# WATERALARM_V1_2.net
KiCad netlist of a schematic drawn in Altium Designer
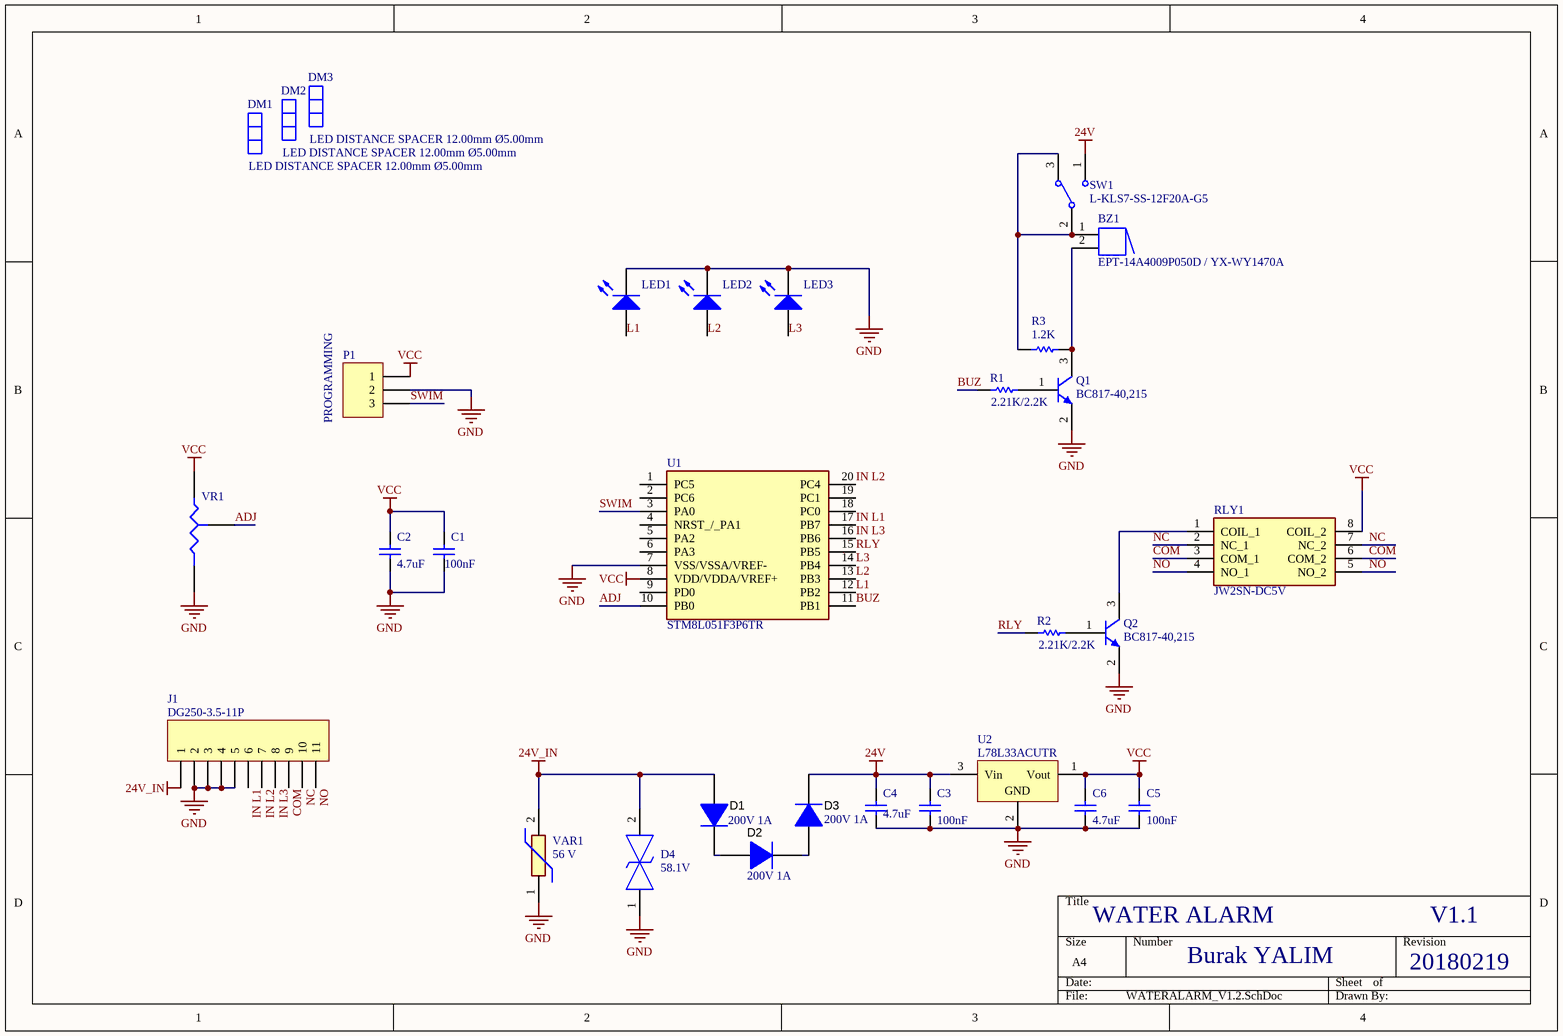
[diagram p0: WATERALARM_V1.2.SchDoc]

(export (version "E")
  (design (tool "Eeschema 10.0.6"))
  (components
    (comp (ref "BZ1")
      (value "EPT-14A4009P050D / YX-WY1470A")
      (footprint "piezo buzzer")
      (description "BUZZER PIEZO W/O CIRCUIT 9V 4-KHZ THT")
      (fields (field (name "MANUFACTURER") "SANCO / YXDZ"))
      (libsource (lib "Miscellaneous Devices") (part "Buzzer"))
    )
    (comp (ref "C1")
      (value "100nF")
      (footprint "C0805-N")
      (description "MLCC (2012) 0805 100nF 50VDC ±10% X7R")
      (fields
        (field (name "MANUFACTURER") "SAMSUNG")
        (field (name "MANUFACTURER PART NUMBER") "CL21B104KBCNNNL")
      )
      (libsource (lib "Miscellaneous Devices") (part "Cap"))
    )
    (comp (ref "C2")
      (value "4.7uF")
      (footprint "C0805-N")
      (description "MLCC (2012) 0805 4.7uF 50VDC ±10% X5R")
      (fields
        (field (name "MANUFACTURER") "SAMSUNG")
        (field (name "MANUFACTURER PART NUMBER") "CL21A475KBQNNNE")
      )
      (libsource (lib "Miscellaneous Devices") (part "Cap"))
    )
    (comp (ref "C3")
      (value "100nF")
      (footprint "C0805-N")
      (description "MLCC (2012) 0805 100nF 50VDC ±10% X7R")
      (fields
        (field (name "MANUFACTURER") "SAMSUNG")
        (field (name "MANUFACTURER PART NUMBER") "CL21B104KBCNNNL")
      )
      (libsource (lib "Miscellaneous Devices") (part "Cap"))
    )
    (comp (ref "C4")
      (value "4.7uF")
      (footprint "C0805-N")
      (description "MLCC (2012) 0805 4.7uF 50VDC ±10% X5R")
      (fields
        (field (name "MANUFACTURER") "SAMSUNG")
        (field (name "MANUFACTURER PART NUMBER") "CL21A475KBQNNNE")
      )
      (libsource (lib "Miscellaneous Devices") (part "Cap"))
    )
    (comp (ref "C5")
      (value "100nF")
      (footprint "C0805-N")
      (description "MLCC (2012) 0805 100nF 50VDC ±10% X7R")
      (fields
        (field (name "MANUFACTURER") "SAMSUNG")
        (field (name "MANUFACTURER PART NUMBER") "CL21B104KBCNNNL")
      )
      (libsource (lib "Miscellaneous Devices") (part "Cap"))
    )
    (comp (ref "C6")
      (value "4.7uF")
      (footprint "C0805-N")
      (description "MLCC (2012) 0805 4.7uF 50VDC ±10% X5R")
      (fields
        (field (name "MANUFACTURER") "SAMSUNG")
        (field (name "MANUFACTURER PART NUMBER") "CL21A475KBQNNNE")
      )
      (libsource (lib "Miscellaneous Devices") (part "Cap"))
    )
    (comp (ref "D1")
      (value "200V 1A")
      (footprint "SMA")
      (description "DIODE U.FAST SINGLE 1A 200V DO214AC (SMA) SMT")
      (fields
        (field (name "MANUFACTURER PART NUMBER") "US1D_R1_00001 / US1D-SMA-MDD")
        (field (name "MANUFACTURER") "ON Semiconductor /  MDD(Microdiode Semiconductor)")
      )
      (libsource (lib "PMP30720_RevA") (part "MURA160T3G"))
    )
    (comp (ref "D2")
      (value "200V 1A")
      (footprint "SMA")
      (description "DIODE U.FAST SINGLE 1A 200V DO214AC (SMA) SMT")
      (fields
        (field (name "MANUFACTURER PART NUMBER") "US1D_R1_00001 / US1D-SMA-MDD")
        (field (name "MANUFACTURER") "ON Semiconductor /  MDD(Microdiode Semiconductor)")
      )
      (libsource (lib "PMP30720_RevA") (part "MURA160T3G"))
    )
    (comp (ref "D3")
      (value "200V 1A")
      (footprint "SMA")
      (description "DIODE U.FAST SINGLE 1A 200V DO214AC (SMA) SMT")
      (fields
        (field (name "MANUFACTURER PART NUMBER") "US1D_R1_00001 / US1D-SMA-MDD")
        (field (name "MANUFACTURER") "ON Semiconductor /  MDD(Microdiode Semiconductor)")
      )
      (libsource (lib "PMP30720_RevA") (part "MURA160T3G"))
    )
    (comp (ref "D4")
      (value "58.1V")
      (footprint "SamacSys:DIONM5127X250N")
      (description "58.1V Clamp 6.9A Ipp Tvs Diode Surface Mount DO-214AC (SMA)")
      (fields
        (field (name "MANUFACTURER") "YAGEO / MDD(Microdiode Semiconductor)")
        (field (name "MANUFACTURER PART NUMBER") "SMAJ36CA/TR7 / SMAJ36CA-UMW")
      )
      (libsource (lib "*") (part "SMAJ36CA-AT_TR7"))
    )
    (comp (ref "DM1")
      (value "LED DISTANCE SPACER 12.00mm Ø5.00mm")
      (description "LED DISTANCE SPACER 12.00mm NONE Ø5.00mm")
      (fields
        (field (name "MANUFACTURER") "KLS ELECTRONIC")
        (field (name "MANUFACTURER PART NUMBER") "L-KLS8-0108-LED-12")
      )
      (libsource (lib "GentekConnectorLib") (part "DISTANCE 11MM M3"))
    )
    (comp (ref "DM2")
      (value "LED DISTANCE SPACER 12.00mm Ø5.00mm")
      (description "LED DISTANCE SPACER 12.00mm NONE Ø5.00mm")
      (fields
        (field (name "MANUFACTURER") "KLS ELECTRONIC")
        (field (name "MANUFACTURER PART NUMBER") "L-KLS8-0108-LED-12")
      )
      (libsource (lib "GentekConnectorLib") (part "DISTANCE 11MM M3"))
    )
    (comp (ref "DM3")
      (value "LED DISTANCE SPACER 12.00mm Ø5.00mm")
      (description "LED DISTANCE SPACER 12.00mm NONE Ø5.00mm")
      (fields
        (field (name "MANUFACTURER") "KLS ELECTRONIC")
        (field (name "MANUFACTURER PART NUMBER") "L-KLS8-0108-LED-12")
      )
      (libsource (lib "GentekConnectorLib") (part "DISTANCE 11MM M3"))
    )
    (comp (ref "J1")
      (value "DG250-3.5-11P")
      (footprint "11 pin Terminal sping loaded")
      (description "TERM.BLK.3.50MM 11P PCB TYPE GRAY GAOSONG")
      (fields (field (name "MANUFACTURER") "DEGSON/GAOSONG"))
      (libsource (lib "WATERALARM_V1.1") (part "DG250-3.5-11P"))
    )
    (comp (ref "LED1")
      (value "3R4HD-7-TB")
      (footprint "led 3mm")
      (description "LED 3MM RED 30mcd 35° RED/DIFFUSED")
      (fields (field (name "MANUFACTURER") "STRONG BASE"))
      (libsource (lib "Miscellaneous Devices") (part "LED2"))
    )
    (comp (ref "LED2")
      (value "3R4HD-7-TB")
      (footprint "led 3mm")
      (description "LED 3MM RED 30mcd 35° RED/DIFFUSED")
      (fields (field (name "MANUFACTURER") "STRONG BASE"))
      (libsource (lib "Miscellaneous Devices") (part "LED2"))
    )
    (comp (ref "LED3")
      (value "3R4HD-7-TB")
      (footprint "led 3mm")
      (description "LED 3MM RED 30mcd 35° RED/DIFFUSED")
      (fields (field (name "MANUFACTURER") "STRONG BASE"))
      (libsource (lib "Miscellaneous Devices") (part "LED2"))
    )
    (comp (ref "P1")
      (value "PROGRAMMING")
      (footprint "HDR1X3")
      (description "Header, 3-Pin")
      (libsource (lib "Miscellaneous Connectors") (part "Header 3"))
    )
    (comp (ref "Q1")
      (value "BC817-40,215")
      (footprint "SOT-23")
      (description "TRANSISTOR DIS.500mA 45V NPN SOT23 GEN. SMT")
      (fields (field (name "MANUFACTURER") "NXP"))
      (libsource (lib "Miscellaneous Devices") (part "NPN"))
    )
    (comp (ref "Q2")
      (value "BC817-40,215")
      (footprint "SOT-23")
      (description "TRANSISTOR DIS.500mA 45V NPN SOT23 GEN. SMT")
      (fields (field (name "MANUFACTURER") "NXP"))
      (libsource (lib "Miscellaneous Devices") (part "NPN"))
    )
    (comp (ref "R1")
      (value "2.21K/2.2K")
      (footprint "C0805-N")
      (description "RES.(2012) 0805 2.21K/2.2K Ohms 1%/5% 1/8W-S 100PPM")
      (fields
        (field (name "MANUFACTURER") "ROYALOHM")
        (field (name "MANUFACTURER PART NUMBER") "0805S8F2211T5E/0805S8J0222T5E")
      )
      (libsource (lib "Miscellaneous Devices") (part "Res1"))
    )
    (comp (ref "R2")
      (value "2.21K/2.2K")
      (footprint "C0805-N")
      (description "RES.(2012) 0805 2.21K/2.2K Ohms 1%/5% 1/8W-S 100PPM")
      (fields
        (field (name "MANUFACTURER") "ROYALOHM")
        (field (name "MANUFACTURER PART NUMBER") "0805S8F2211T5E/0805S8J0222T5E")
      )
      (libsource (lib "Miscellaneous Devices") (part "Res1"))
    )
    (comp (ref "R3")
      (value "1.2K")
      (footprint "C1210")
      (description "RES.(3225) 1210 1.2K Ohms 5% 1/2W 200PPM")
      (fields
        (field (name "MANUFACTURER") "HOTTECH")
        (field (name "MANUFACTURER PART NUMBER") "RI1210L122JT")
      )
      (libsource (lib "Miscellaneous Devices") (part "Res1"))
    )
    (comp (ref "RLY1")
      (value "JW2SN-DC5V")
      (footprint "SamacSys:JW2SNDC5V")
      (description "General Purpose Relay DPDT (2 Form C) 5VDC Coil Through Hole")
      (fields (field (name "MANUFACTURER") "Panasonic"))
      (libsource (lib "*") (part "JW2SN-DC5V"))
    )
    (comp (ref "SW1")
      (value "L-KLS7-SS-12F20A-G5")
      (footprint "Slide Switch")
      (description "SWITCH SLIDE 1P2T 500mA 50V On-On THT V/T")
      (fields (field (name "MANUFACTURER") "KLS ELECTRONIC"))
      (libsource (lib "Miscellaneous Devices") (part "SW-SPDT"))
    )
    (comp (ref "U1")
      (value "STM8L051F3P6TR")
      (footprint "SamacSys:SOP65P640X120-20N")
      (description "IC-8L051 MCU 8BIT 8K FLASH TSSOP20")
      (fields
        (field (name "MANUFACTURER") "STMicroelectronics")
        (field (name "MOUSER PART NUMBER") "511-STM8L051F3P6TR")
      )
      (libsource (lib "*") (part "STM8L051F3P6TR"))
    )
    (comp (ref "U2")
      (value "L78L33ACUTR")
      (footprint "SOT89M")
      (description "IC-78L33 VOLTAGE REGULATOR 3.3V 100mA SOT89 ST")
      (fields (field (name "MANUFACTURER") "STM"))
      (libsource (lib "Miscellaneous Devices") (part "Volt Reg"))
    )
    (comp (ref "VAR1")
      (value "TVR07470KSY")
      (footprint "SamacSys:ERZV05D180")
      (description "VARISTOR DISC 7MM 47V 250A 30VAC 38VDC THT")
      (fields (field (name "VARISTOR VOLTAGE") "56 V") (field (name "MANUFACTURER") "THINKING"))
      (libsource (lib "*") (part "ERZ-V05D180"))
    )
    (comp (ref "VR1")
      (value "L-KLS4-WH06-2A-103")
      (footprint "Potentiometer")
      (description "TRIMPOT CARBON V 6MM 10K")
      (fields (field (name "MANUFACTURER") "KLS ELECTRONIC"))
      (libsource (lib "Miscellaneous Devices") (part "Res Tap"))
    )
  )
  (nets
    (net (code "1") (name "/ADJ") (class "Default")
      (node (ref "U1") (pin "10") (pinfunction "PB0_10") (pintype "passive"))
      (node (ref "VR1") (pin "3") (pinfunction "TAP_3") (pintype "passive"))
    )
    (net (code "2") (name "/BUZ") (class "Default")
      (node (ref "R1") (pin "2") (pinfunction "2_2") (pintype "passive"))
      (node (ref "U1") (pin "11") (pinfunction "PB1_11") (pintype "passive"))
    )
    (net (code "3") (name "/COM") (class "Default")
      (node (ref "J1") (pin "9") (pinfunction "9_9") (pintype "passive"))
      (node (ref "RLY1") (pin "3") (pinfunction "COM_1_3") (pintype "passive"))
      (node (ref "RLY1") (pin "6") (pinfunction "COM_2_6") (pintype "passive"))
    )
    (net (code "4") (name "/IN L1") (class "Default")
      (node (ref "J1") (pin "6") (pinfunction "6_6") (pintype "passive"))
      (node (ref "U1") (pin "17") (pinfunction "PB7_17") (pintype "passive"))
    )
    (net (code "5") (name "/IN L2") (class "Default")
      (node (ref "J1") (pin "7") (pinfunction "7_7") (pintype "passive"))
      (node (ref "U1") (pin "20") (pinfunction "PC4_20") (pintype "passive"))
    )
    (net (code "6") (name "/IN L3") (class "Default")
      (node (ref "J1") (pin "8") (pinfunction "8_8") (pintype "passive"))
      (node (ref "U1") (pin "16") (pinfunction "PB6_16") (pintype "passive"))
    )
    (net (code "7") (name "/L1") (class "Default")
      (node (ref "LED1") (pin "1") (pinfunction "A_1") (pintype "passive"))
      (node (ref "U1") (pin "12") (pinfunction "PB2_12") (pintype "passive"))
    )
    (net (code "8") (name "/L2") (class "Default")
      (node (ref "LED2") (pin "1") (pinfunction "A_1") (pintype "passive"))
      (node (ref "U1") (pin "13") (pinfunction "PB3_13") (pintype "passive"))
    )
    (net (code "9") (name "/L3") (class "Default")
      (node (ref "LED3") (pin "1") (pinfunction "A_1") (pintype "passive"))
      (node (ref "U1") (pin "14") (pinfunction "PB4_14") (pintype "passive"))
    )
    (net (code "10") (name "/NC") (class "Default")
      (node (ref "J1") (pin "10") (pinfunction "10_10") (pintype "passive"))
      (node (ref "RLY1") (pin "2") (pinfunction "NC_1_2") (pintype "passive"))
      (node (ref "RLY1") (pin "7") (pinfunction "NC_2_7") (pintype "passive"))
    )
    (net (code "11") (name "/NO") (class "Default")
      (node (ref "J1") (pin "11") (pinfunction "11_11") (pintype "passive"))
      (node (ref "RLY1") (pin "4") (pinfunction "NO_1_4") (pintype "passive"))
      (node (ref "RLY1") (pin "5") (pinfunction "NO_2_5") (pintype "passive"))
    )
    (net (code "12") (name "/RLY") (class "Default")
      (node (ref "R2") (pin "2") (pinfunction "2_2") (pintype "passive"))
      (node (ref "U1") (pin "15") (pinfunction "PB5_15") (pintype "passive"))
    )
    (net (code "13") (name "/SWIM") (class "Default")
      (node (ref "P1") (pin "3") (pinfunction "3_3") (pintype "passive"))
      (node (ref "U1") (pin "3") (pinfunction "PA0_3") (pintype "passive"))
    )
    (net (code "14") (name "24V") (class "Default")
      (node (ref "C3") (pin "2") (pinfunction "2_2") (pintype "passive"))
      (node (ref "C4") (pin "2") (pinfunction "2_2") (pintype "passive"))
      (node (ref "D3") (pin "1") (pinfunction "K_1") (pintype "passive"))
      (node (ref "SW1") (pin "1") (pinfunction "1_1") (pintype "passive"))
      (node (ref "U2") (pin "3") (pinfunction "Vin_3") (pintype "passive"))
    )
    (net (code "15") (name "24V_IN") (class "Default")
      (node (ref "D1") (pin "2") (pinfunction "A_2") (pintype "passive"))
      (node (ref "D4") (pin "2") (pinfunction "2_2") (pintype "passive"))
      (node (ref "J1") (pin "1") (pinfunction "1_1") (pintype "passive"))
      (node (ref "VAR1") (pin "2") (pinfunction "2_2") (pintype "passive"))
    )
    (net (code "16") (name "GND") (class "Default")
      (node (ref "C1") (pin "1") (pinfunction "1_1") (pintype "passive"))
      (node (ref "C2") (pin "1") (pinfunction "1_1") (pintype "passive"))
      (node (ref "C3") (pin "1") (pinfunction "1_1") (pintype "passive"))
      (node (ref "C4") (pin "1") (pinfunction "1_1") (pintype "passive"))
      (node (ref "C5") (pin "1") (pinfunction "1_1") (pintype "passive"))
      (node (ref "C6") (pin "1") (pinfunction "1_1") (pintype "passive"))
      (node (ref "D4") (pin "1") (pinfunction "1_1") (pintype "passive"))
      (node (ref "J1") (pin "2") (pinfunction "2_2") (pintype "passive"))
      (node (ref "J1") (pin "3") (pinfunction "3_3") (pintype "passive"))
      (node (ref "J1") (pin "4") (pinfunction "4_4") (pintype "passive"))
      (node (ref "J1") (pin "5") (pinfunction "5_5") (pintype "passive"))
      (node (ref "LED1") (pin "2") (pinfunction "K_2") (pintype "passive"))
      (node (ref "LED2") (pin "2") (pinfunction "K_2") (pintype "passive"))
      (node (ref "LED3") (pin "2") (pinfunction "K_2") (pintype "passive"))
      (node (ref "P1") (pin "2") (pinfunction "2_2") (pintype "passive"))
      (node (ref "Q1") (pin "2") (pinfunction "E_2") (pintype "passive"))
      (node (ref "Q2") (pin "2") (pinfunction "E_2") (pintype "passive"))
      (node (ref "U1") (pin "7") (pinfunction "VSS/VSSA/VREF-_7") (pintype "passive"))
      (node (ref "U2") (pin "2") (pinfunction "GND_2") (pintype "passive"))
      (node (ref "VAR1") (pin "1") (pinfunction "1_1") (pintype "passive"))
      (node (ref "VR1") (pin "2") (pinfunction "B_2") (pintype "passive"))
    )
    (net (code "17") (name "Net-(BZ1-Pad1)") (class "Default")
      (node (ref "BZ1") (pin "1") (pinfunction "1_1") (pintype "passive"))
      (node (ref "R3") (pin "2") (pinfunction "2_2") (pintype "passive"))
      (node (ref "SW1") (pin "2") (pinfunction "2_2") (pintype "passive"))
      (node (ref "SW1") (pin "3") (pinfunction "3_3") (pintype "passive"))
    )
    (net (code "18") (name "Net-(D1-K)") (class "Default")
      (node (ref "D1") (pin "1") (pinfunction "K_1") (pintype "passive"))
      (node (ref "D2") (pin "2") (pinfunction "A_2") (pintype "passive"))
    )
    (net (code "19") (name "Net-(D2-K)") (class "Default")
      (node (ref "D2") (pin "1") (pinfunction "K_1") (pintype "passive"))
      (node (ref "D3") (pin "2") (pinfunction "A_2") (pintype "passive"))
    )
    (net (code "20") (name "Net-(Q1-B)") (class "Default")
      (node (ref "Q1") (pin "1") (pinfunction "B_1") (pintype "passive"))
      (node (ref "R1") (pin "1") (pinfunction "1_1") (pintype "passive"))
    )
    (net (code "21") (name "Net-(Q1-C)") (class "Default")
      (node (ref "BZ1") (pin "2") (pinfunction "2_2") (pintype "passive"))
      (node (ref "Q1") (pin "3") (pinfunction "C_3") (pintype "passive"))
      (node (ref "R3") (pin "1") (pinfunction "1_1") (pintype "passive"))
    )
    (net (code "22") (name "Net-(Q2-B)") (class "Default")
      (node (ref "Q2") (pin "1") (pinfunction "B_1") (pintype "passive"))
      (node (ref "R2") (pin "1") (pinfunction "1_1") (pintype "passive"))
    )
    (net (code "23") (name "Net-(Q2-C)") (class "Default")
      (node (ref "Q2") (pin "3") (pinfunction "C_3") (pintype "passive"))
      (node (ref "RLY1") (pin "1") (pinfunction "COIL_1_1") (pintype "passive"))
    )
    (net (code "24") (name "VCC") (class "Default")
      (node (ref "C1") (pin "2") (pinfunction "2_2") (pintype "passive"))
      (node (ref "C2") (pin "2") (pinfunction "2_2") (pintype "passive"))
      (node (ref "C5") (pin "2") (pinfunction "2_2") (pintype "passive"))
      (node (ref "C6") (pin "2") (pinfunction "2_2") (pintype "passive"))
      (node (ref "P1") (pin "1") (pinfunction "1_1") (pintype "passive"))
      (node (ref "RLY1") (pin "8") (pinfunction "COIL_2_8") (pintype "passive"))
      (node (ref "U1") (pin "8") (pinfunction "VDD/VDDA/VREF+_8") (pintype "passive"))
      (node (ref "U2") (pin "1") (pinfunction "Vout_1") (pintype "passive"))
      (node (ref "VR1") (pin "1") (pinfunction "A_1") (pintype "passive"))
    )
    (net (code "25") (name "unconnected-(U1-NRST_{slash}_PA1-Pad4)") (class "Default")
      (node (ref "U1") (pin "4") (pinfunction "NRST_/_PA1_4") (pintype "passive"))
    )
    (net (code "26") (name "unconnected-(U1-PA2-Pad5)") (class "Default")
      (node (ref "U1") (pin "5") (pinfunction "PA2_5") (pintype "passive"))
    )
    (net (code "27") (name "unconnected-(U1-PA3-Pad6)") (class "Default")
      (node (ref "U1") (pin "6") (pinfunction "PA3_6") (pintype "passive"))
    )
    (net (code "28") (name "unconnected-(U1-PC0-Pad18)") (class "Default")
      (node (ref "U1") (pin "18") (pinfunction "PC0_18") (pintype "passive"))
    )
    (net (code "29") (name "unconnected-(U1-PC1-Pad19)") (class "Default")
      (node (ref "U1") (pin "19") (pinfunction "PC1_19") (pintype "passive"))
    )
    (net (code "30") (name "unconnected-(U1-PC5-Pad1)") (class "Default")
      (node (ref "U1") (pin "1") (pinfunction "PC5_1") (pintype "passive"))
    )
    (net (code "31") (name "unconnected-(U1-PC6-Pad2)") (class "Default")
      (node (ref "U1") (pin "2") (pinfunction "PC6_2") (pintype "passive"))
    )
    (net (code "32") (name "unconnected-(U1-PD0-Pad9)") (class "Default")
      (node (ref "U1") (pin "9") (pinfunction "PD0_9") (pintype "passive"))
    )
  )
)
